# AFE.net
KiCad netlist of a schematic drawn in Altium Designer
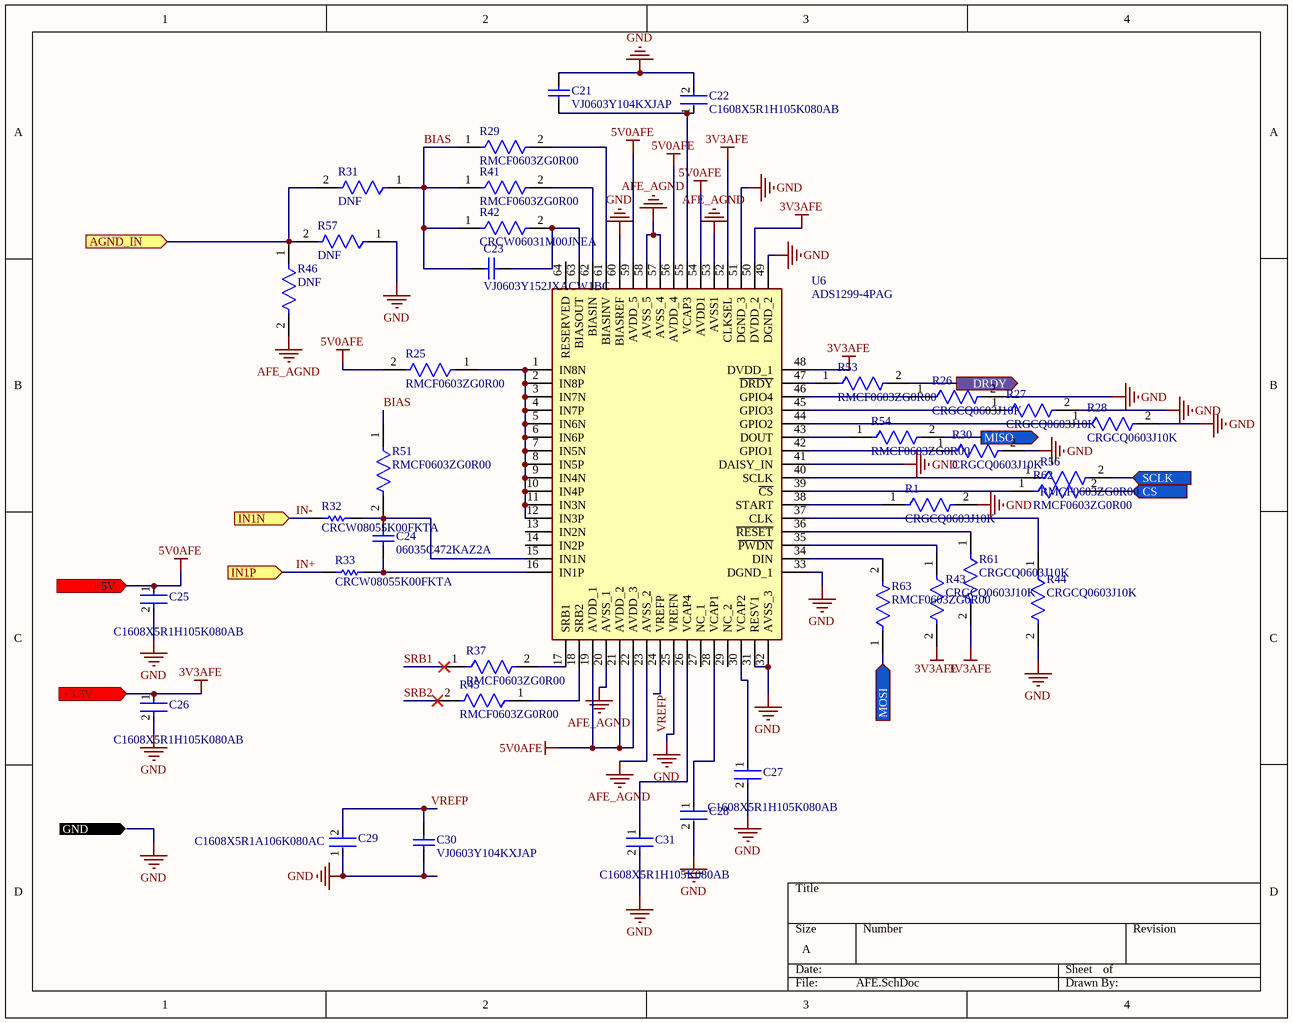
[diagram p0: AFE.SchDoc]

(export (version "E")
  (design (tool "Eeschema 10.0.6"))
  (components
    (comp (ref "C21")
      (value "VJ0603Y104KXJAP")
      (footprint "CAPC1608X92X38NL15T08")
      (fields (field (name "MANUFACTURER") "Vitramon"))
      (libsource (lib "Altium Content Vault") (part "CAP"))
    )
    (comp (ref "C22")
      (value "C1608X5R1H105K080AB")
      (footprint "FP-C1608-080-0_1-IPC_B")
      (description "Multilayer Ceramic Capacitors 1μF ±10% 50V X5R SMD 0603")
      (fields (field (name "VOLTAGE") "50V") (field (name "TOLERANCE") "10%"))
      (libsource (lib "Altium Content Vault") (part "236180d848d6139a670b325ea6854c9"))
    )
    (comp (ref "C23")
      (value "VJ0603Y152JXACW1BC")
      (footprint "CAPC1608X95X40NL15T15")
      (fields (field (name "MANUFACTURER") "Vitramon"))
      (libsource (lib "Altium Content Vault") (part "CAP"))
    )
    (comp (ref "C24")
      (value "06035C472KAZ2A")
      (footprint "CAPC1608X90X35LL15T15")
      (fields (field (name "MANUFACTURER") "AVX Interconnect / Elco"))
      (libsource (lib "Altium Content Vault") (part "CAP"))
    )
    (comp (ref "C25")
      (value "C1608X5R1H105K080AB")
      (footprint "FP-C1608-080-0_1-IPC_B")
      (description "Multilayer Ceramic Capacitors 1μF ±10% 50V X5R SMD 0603")
      (fields (field (name "VOLTAGE") "50V") (field (name "TOLERANCE") "10%"))
      (libsource (lib "Altium Content Vault") (part "236180d848d6139a670b325ea6854c9"))
    )
    (comp (ref "C26")
      (value "C1608X5R1H105K080AB")
      (footprint "FP-C1608-080-0_1-IPC_B")
      (description "Multilayer Ceramic Capacitors 1μF ±10% 50V X5R SMD 0603")
      (fields (field (name "VOLTAGE") "50V") (field (name "TOLERANCE") "10%"))
      (libsource (lib "Altium Content Vault") (part "236180d848d6139a670b325ea6854c9"))
    )
    (comp (ref "C27")
      (value "C1608X5R1H105K080AB")
      (footprint "FP-C1608-080-0_1-IPC_B")
      (description "Multilayer Ceramic Capacitors 1μF ±10% 50V X5R SMD 0603")
      (fields (field (name "VOLTAGE") "50V") (field (name "TOLERANCE") "10%"))
      (libsource (lib "Altium Content Vault") (part "236180d848d6139a670b325ea6854c9"))
    )
    (comp (ref "C28")
      (value "GRM21BR60J107ME15K")
      (footprint "FP-GRM21B-0_2-e0_2_0_7-IPC_B")
      (description "Chip Multilayer Ceramic Capacitors for General Purpose, 0805, 100uF, X5R, 15%, 20%, 6.3V")
      (fields (field (name "TOLERANCE") "20%"))
      (libsource (lib "Altium Content Vault") (part "b4654b650e69147ec39a6b967a45e02"))
    )
    (comp (ref "C29")
      (value "C1608X5R1A106K080AC")
      (footprint "FP-C1608-080-0_1-MFG")
      (description "Multilayer Ceramic Capacitors 10μF ±10% 10V X5R SMD 0603")
      (fields (field (name "VOLTAGE") "10V") (field (name "TOLERANCE") "10%"))
      (libsource (lib "Altium Content Vault") (part "236180d848d6139a670b325ea6854c9"))
    )
    (comp (ref "C30")
      (value "VJ0603Y104KXJAP")
      (footprint "CAPC1608X92X38NL15T08")
      (fields (field (name "MANUFACTURER") "Vitramon"))
      (libsource (lib "Altium Content Vault") (part "CAP"))
    )
    (comp (ref "C31")
      (value "C1608X5R1H105K080AB")
      (footprint "FP-C1608-080-0_1-IPC_B")
      (description "Multilayer Ceramic Capacitors 1μF ±10% 50V X5R SMD 0603")
      (fields (field (name "VOLTAGE") "50V") (field (name "TOLERANCE") "10%"))
      (libsource (lib "Altium Content Vault") (part "236180d848d6139a670b325ea6854c9"))
    )
    (comp (ref "R1")
      (value "CRGCQ0603J10K")
      (footprint "FP-CRGCQ0603-IPC_C")
      (description "CRGCQ 0603 10K 5%")
      (fields
        (field (name "TOLERANCE") "0.05")
        (field (name "OCTOPART") "https://octopart.com/crgcq0603j10k-te+connectivity-91018097")
      )
      (libsource (lib "Altium Content Vault") (part "1029c3af85768c4190bb7ad29bc67b5"))
    )
    (comp (ref "R25")
      (value "RMCF0603ZG0R00")
      (footprint "FP-RMCF0603-IPC_B")
      (description "0Ω ±0 0.1W 0603 Thick Film Chip Resistor AEC-Q200 compliant")
      (libsource (lib "Altium Content Vault") (part "1029c3af85768c4190bb7ad29bc67b5"))
    )
    (comp (ref "R26")
      (value "CRGCQ0603J10K")
      (footprint "FP-CRGCQ0603-IPC_C")
      (description "CRGCQ 0603 10K 5%")
      (fields
        (field (name "TOLERANCE") "0.05")
        (field (name "OCTOPART") "https://octopart.com/crgcq0603j10k-te+connectivity-91018097")
      )
      (libsource (lib "Altium Content Vault") (part "1029c3af85768c4190bb7ad29bc67b5"))
    )
    (comp (ref "R27")
      (value "CRGCQ0603J10K")
      (footprint "FP-CRGCQ0603-IPC_C")
      (description "CRGCQ 0603 10K 5%")
      (fields
        (field (name "TOLERANCE") "0.05")
        (field (name "OCTOPART") "https://octopart.com/crgcq0603j10k-te+connectivity-91018097")
      )
      (libsource (lib "Altium Content Vault") (part "1029c3af85768c4190bb7ad29bc67b5"))
    )
    (comp (ref "R28")
      (value "CRGCQ0603J10K")
      (footprint "FP-CRGCQ0603-IPC_C")
      (description "CRGCQ 0603 10K 5%")
      (fields
        (field (name "TOLERANCE") "0.05")
        (field (name "OCTOPART") "https://octopart.com/crgcq0603j10k-te+connectivity-91018097")
      )
      (libsource (lib "Altium Content Vault") (part "1029c3af85768c4190bb7ad29bc67b5"))
    )
    (comp (ref "R29")
      (value "RMCF0603ZG0R00")
      (footprint "FP-RMCF0603-IPC_B")
      (description "0Ω ±0 0.1W 0603 Thick Film Chip Resistor AEC-Q200 compliant")
      (libsource (lib "Altium Content Vault") (part "1029c3af85768c4190bb7ad29bc67b5"))
    )
    (comp (ref "R30")
      (value "CRGCQ0603J10K")
      (footprint "FP-CRGCQ0603-IPC_C")
      (description "CRGCQ 0603 10K 5%")
      (fields
        (field (name "TOLERANCE") "0.05")
        (field (name "OCTOPART") "https://octopart.com/crgcq0603j10k-te+connectivity-91018097")
      )
      (libsource (lib "Altium Content Vault") (part "1029c3af85768c4190bb7ad29bc67b5"))
    )
    (comp (ref "R31")
      (value "DNF")
      (footprint "FP-RMCF0603-IPC_B")
      (description "0Ω ±0 0.1W 0603 Thick Film Chip Resistor AEC-Q200 compliant")
      (libsource (lib "Altium Content Vault") (part "1029c3af85768c4190bb7ad29bc67b5"))
    )
    (comp (ref "R32")
      (value "CRCW08055K00FKTA")
      (footprint "RESC2013X50X30ML20T20")
      (fields (field (name "MANUFACTURER") "Vishay Dale"))
      (libsource (lib "Altium Content Vault") (part "RES"))
    )
    (comp (ref "R33")
      (value "CRCW08055K00FKTA")
      (footprint "RESC2013X50X30ML20T20")
      (fields (field (name "MANUFACTURER") "Vishay Dale"))
      (libsource (lib "Altium Content Vault") (part "RES"))
    )
    (comp (ref "R37")
      (value "RMCF0603ZG0R00")
      (footprint "FP-RMCF0603-IPC_B")
      (description "0Ω ±0 0.1W 0603 Thick Film Chip Resistor AEC-Q200 compliant")
      (libsource (lib "Altium Content Vault") (part "1029c3af85768c4190bb7ad29bc67b5"))
    )
    (comp (ref "R41")
      (value "RMCF0603ZG0R00")
      (footprint "FP-RMCF0603-IPC_B")
      (description "0Ω ±0 0.1W 0603 Thick Film Chip Resistor AEC-Q200 compliant")
      (libsource (lib "Altium Content Vault") (part "1029c3af85768c4190bb7ad29bc67b5"))
    )
    (comp (ref "R42")
      (value "CRCW06031M00JNEA")
      (footprint "FP-CRCW0603-e3-IPC_B")
      (description "RES Thick Film, 1MΩ, 5%, 0.1W, 200ppm/°C, 0603")
      (fields (field (name "TOLERANCE") "5%"))
      (libsource (lib "Altium Content Vault") (part "1029c3af85768c4190bb7ad29bc67b5"))
    )
    (comp (ref "R43")
      (value "CRGCQ0603J10K")
      (footprint "FP-CRGCQ0603-IPC_C")
      (description "CRGCQ 0603 10K 5%")
      (fields
        (field (name "TOLERANCE") "0.05")
        (field (name "OCTOPART") "https://octopart.com/crgcq0603j10k-te+connectivity-91018097")
      )
      (libsource (lib "Altium Content Vault") (part "1029c3af85768c4190bb7ad29bc67b5"))
    )
    (comp (ref "R44")
      (value "CRGCQ0603J10K")
      (footprint "FP-CRGCQ0603-IPC_C")
      (description "CRGCQ 0603 10K 5%")
      (fields
        (field (name "TOLERANCE") "0.05")
        (field (name "OCTOPART") "https://octopart.com/crgcq0603j10k-te+connectivity-91018097")
      )
      (libsource (lib "Altium Content Vault") (part "1029c3af85768c4190bb7ad29bc67b5"))
    )
    (comp (ref "R45")
      (value "RMCF0603ZG0R00")
      (footprint "FP-RMCF0603-IPC_B")
      (description "0Ω ±0 0.1W 0603 Thick Film Chip Resistor AEC-Q200 compliant")
      (libsource (lib "Altium Content Vault") (part "1029c3af85768c4190bb7ad29bc67b5"))
    )
    (comp (ref "R46")
      (value "DNF")
      (footprint "FP-RMCF0603-IPC_B")
      (description "0Ω ±0 0.1W 0603 Thick Film Chip Resistor AEC-Q200 compliant")
      (libsource (lib "Altium Content Vault") (part "1029c3af85768c4190bb7ad29bc67b5"))
    )
    (comp (ref "R51")
      (value "RMCF0603ZG0R00")
      (footprint "FP-RMCF0603-IPC_B")
      (description "0Ω ±0 0.1W 0603 Thick Film Chip Resistor AEC-Q200 compliant")
      (libsource (lib "Altium Content Vault") (part "1029c3af85768c4190bb7ad29bc67b5"))
    )
    (comp (ref "R53")
      (value "RMCF0603ZG0R00")
      (footprint "FP-RMCF0603-IPC_B")
      (description "0Ω ±0 0.1W 0603 Thick Film Chip Resistor AEC-Q200 compliant")
      (libsource (lib "Altium Content Vault") (part "1029c3af85768c4190bb7ad29bc67b5"))
    )
    (comp (ref "R54")
      (value "RMCF0603ZG0R00")
      (footprint "FP-RMCF0603-IPC_B")
      (description "0Ω ±0 0.1W 0603 Thick Film Chip Resistor AEC-Q200 compliant")
      (libsource (lib "Altium Content Vault") (part "1029c3af85768c4190bb7ad29bc67b5"))
    )
    (comp (ref "R56")
      (value "RMCF0603ZG0R00")
      (footprint "FP-RMCF0603-IPC_B")
      (description "0Ω ±0 0.1W 0603 Thick Film Chip Resistor AEC-Q200 compliant")
      (libsource (lib "Altium Content Vault") (part "1029c3af85768c4190bb7ad29bc67b5"))
    )
    (comp (ref "R57")
      (value "DNF")
      (footprint "FP-RMCF0603-IPC_B")
      (description "0Ω ±0 0.1W 0603 Thick Film Chip Resistor AEC-Q200 compliant")
      (libsource (lib "Altium Content Vault") (part "1029c3af85768c4190bb7ad29bc67b5"))
    )
    (comp (ref "R61")
      (value "CRGCQ0603J10K")
      (footprint "FP-CRGCQ0603-IPC_C")
      (description "CRGCQ 0603 10K 5%")
      (fields
        (field (name "TOLERANCE") "0.05")
        (field (name "OCTOPART") "https://octopart.com/crgcq0603j10k-te+connectivity-91018097")
      )
      (libsource (lib "Altium Content Vault") (part "1029c3af85768c4190bb7ad29bc67b5"))
    )
    (comp (ref "R62")
      (value "RMCF0603ZG0R00")
      (footprint "FP-RMCF0603-IPC_B")
      (description "0Ω ±0 0.1W 0603 Thick Film Chip Resistor AEC-Q200 compliant")
      (libsource (lib "Altium Content Vault") (part "1029c3af85768c4190bb7ad29bc67b5"))
    )
    (comp (ref "R63")
      (value "RMCF0603ZG0R00")
      (footprint "FP-RMCF0603-IPC_B")
      (description "0Ω ±0 0.1W 0603 Thick Film Chip Resistor AEC-Q200 compliant")
      (libsource (lib "Altium Content Vault") (part "1029c3af85768c4190bb7ad29bc67b5"))
    )
    (comp (ref "U6")
      (value "ADS1299-4PAG")
      (footprint "QFP50P1200X1200X120-64N")
      (description "Low-Noise, 4-Channel, 24-Bit Analog-to-Digital Converter for Biopotential Measurements")
      (fields (field (name "MOUSER PART NUMBER") "595-ADS1299-4PAG"))
      (libsource (lib "ADS1299-4PAG") (part "ADS1299-4PAG"))
    )
  )
  (nets
    (net (code "1") (name "/AGND_IN") (class "Default")
      (node (ref "R31") (pin "2") (pinfunction "2_2") (pintype "passive"))
      (node (ref "R46") (pin "1") (pinfunction "1_1") (pintype "passive"))
      (node (ref "R57") (pin "2") (pinfunction "2_2") (pintype "passive"))
    )
    (net (code "2") (name "/BIAS") (class "Default")
      (node (ref "C23") (pin "1") (pinfunction "1_1") (pintype "passive"))
      (node (ref "R29") (pin "1") (pinfunction "1_1") (pintype "passive"))
      (node (ref "R31") (pin "1") (pinfunction "1_1") (pintype "passive"))
      (node (ref "R41") (pin "1") (pinfunction "1_1") (pintype "passive"))
      (node (ref "R42") (pin "1") (pinfunction "1_1") (pintype "passive"))
      (node (ref "R51") (pin "1") (pinfunction "1_1") (pintype "passive"))
    )
    (net (code "3") (name "/CS") (class "Default")
      (node (ref "R62") (pin "2") (pinfunction "2_2") (pintype "passive"))
    )
    (net (code "4") (name "/DRDY") (class "Default")
      (node (ref "R53") (pin "2") (pinfunction "2_2") (pintype "passive"))
    )
    (net (code "5") (name "/IN+") (class "Default")
      (node (ref "R33") (pin "1") (pinfunction "1_1") (pintype "passive"))
    )
    (net (code "6") (name "/IN-") (class "Default")
      (node (ref "R32") (pin "1") (pinfunction "1_1") (pintype "passive"))
    )
    (net (code "7") (name "/MISO") (class "Default")
      (node (ref "R54") (pin "2") (pinfunction "2_2") (pintype "passive"))
    )
    (net (code "8") (name "/MOSI") (class "Default")
      (node (ref "R63") (pin "1") (pinfunction "1_1") (pintype "passive"))
    )
    (net (code "9") (name "/SCLK") (class "Default")
      (node (ref "R56") (pin "2") (pinfunction "2_2") (pintype "passive"))
    )
    (net (code "10") (name "/SRB1") (class "Default")
      (node (ref "R37") (pin "1") (pinfunction "1_1") (pintype "passive+no_connect"))
    )
    (net (code "11") (name "/SRB2") (class "Default")
      (node (ref "R45") (pin "2") (pinfunction "2_2") (pintype "passive+no_connect"))
    )
    (net (code "12") (name "/VREFP") (class "Default")
      (node (ref "C29") (pin "2") (pinfunction "2_2") (pintype "passive"))
      (node (ref "C30") (pin "2") (pinfunction "2_2") (pintype "passive"))
      (node (ref "U6") (pin "24") (pinfunction "VREFP_24") (pintype "passive"))
    )
    (net (code "13") (name "3V3AFE") (class "Default")
      (node (ref "C26") (pin "1") (pinfunction "1_1") (pintype "passive"))
      (node (ref "R43") (pin "2") (pinfunction "2_2") (pintype "passive"))
      (node (ref "R61") (pin "2") (pinfunction "2_2") (pintype "passive"))
      (node (ref "U6") (pin "48") (pinfunction "DVDD_1_48") (pintype "passive"))
      (node (ref "U6") (pin "50") (pinfunction "DVDD_2_50") (pintype "passive"))
      (node (ref "U6") (pin "52") (pinfunction "CLKSEL_52") (pintype "passive"))
    )
    (net (code "14") (name "5V0AFE") (class "Default")
      (node (ref "C25") (pin "1") (pinfunction "1_1") (pintype "passive"))
      (node (ref "R25") (pin "2") (pinfunction "2_2") (pintype "passive"))
      (node (ref "U6") (pin "19") (pinfunction "AVDD_1_19") (pintype "passive"))
      (node (ref "U6") (pin "21") (pinfunction "AVDD_2_21") (pintype "passive"))
      (node (ref "U6") (pin "22") (pinfunction "AVDD_3_22") (pintype "passive"))
      (node (ref "U6") (pin "54") (pinfunction "AVDD1_54") (pintype "passive"))
      (node (ref "U6") (pin "56") (pinfunction "AVDD_4_56") (pintype "passive"))
      (node (ref "U6") (pin "59") (pinfunction "AVDD_5_59") (pintype "passive"))
    )
    (net (code "15") (name "AFE_AGND") (class "Default")
      (node (ref "R46") (pin "2") (pinfunction "2_2") (pintype "passive"))
      (node (ref "U6") (pin "20") (pinfunction "AVSS_1_20") (pintype "passive"))
      (node (ref "U6") (pin "23") (pinfunction "AVSS_2_23") (pintype "passive"))
      (node (ref "U6") (pin "53") (pinfunction "AVSS1_53") (pintype "passive"))
      (node (ref "U6") (pin "57") (pinfunction "AVSS_4_57") (pintype "passive"))
      (node (ref "U6") (pin "58") (pinfunction "AVSS_5_58") (pintype "passive"))
    )
    (net (code "16") (name "GND") (class "Default")
      (node (ref "C21") (pin "2") (pinfunction "2_2") (pintype "passive"))
      (node (ref "C22") (pin "2") (pinfunction "2_2") (pintype "passive"))
      (node (ref "C25") (pin "2") (pinfunction "2_2") (pintype "passive"))
      (node (ref "C26") (pin "2") (pinfunction "2_2") (pintype "passive"))
      (node (ref "C27") (pin "2") (pinfunction "2_2") (pintype "passive"))
      (node (ref "C28") (pin "2") (pinfunction "2_2") (pintype "passive"))
      (node (ref "C29") (pin "1") (pinfunction "1_1") (pintype "passive"))
      (node (ref "C30") (pin "1") (pinfunction "1_1") (pintype "passive"))
      (node (ref "C31") (pin "2") (pinfunction "2_2") (pintype "passive"))
      (node (ref "R1") (pin "2") (pinfunction "2_2") (pintype "passive"))
      (node (ref "R26") (pin "2") (pinfunction "2_2") (pintype "passive"))
      (node (ref "R27") (pin "2") (pinfunction "2_2") (pintype "passive"))
      (node (ref "R28") (pin "2") (pinfunction "2_2") (pintype "passive"))
      (node (ref "R30") (pin "2") (pinfunction "2_2") (pintype "passive"))
      (node (ref "R44") (pin "2") (pinfunction "2_2") (pintype "passive"))
      (node (ref "R57") (pin "1") (pinfunction "1_1") (pintype "passive"))
      (node (ref "U6") (pin "25") (pinfunction "VREFN_25") (pintype "passive"))
      (node (ref "U6") (pin "31") (pinfunction "RESV1_31") (pintype "passive"))
      (node (ref "U6") (pin "32") (pinfunction "AVSS_3_32") (pintype "passive"))
      (node (ref "U6") (pin "33") (pinfunction "DGND_1_33") (pintype "passive"))
      (node (ref "U6") (pin "41") (pinfunction "DAISY_IN_41") (pintype "passive"))
      (node (ref "U6") (pin "49") (pinfunction "DGND_2_49") (pintype "passive"))
      (node (ref "U6") (pin "51") (pinfunction "DGND_3_51") (pintype "passive"))
      (node (ref "U6") (pin "60") (pinfunction "BIASREF_60") (pintype "passive"))
    )
    (net (code "17") (name "Net-(U6-BIASIN)") (class "Default")
      (node (ref "R41") (pin "2") (pinfunction "2_2") (pintype "passive"))
      (node (ref "U6") (pin "62") (pinfunction "BIASIN_62") (pintype "passive"))
    )
    (net (code "18") (name "Net-(U6-BIASINV)") (class "Default")
      (node (ref "R29") (pin "2") (pinfunction "2_2") (pintype "passive"))
      (node (ref "U6") (pin "61") (pinfunction "BIASINV_61") (pintype "passive"))
    )
    (net (code "19") (name "Net-(U6-BIASOUT)") (class "Default")
      (node (ref "C23") (pin "2") (pinfunction "2_2") (pintype "passive"))
      (node (ref "R42") (pin "2") (pinfunction "2_2") (pintype "passive"))
      (node (ref "U6") (pin "63") (pinfunction "BIASOUT_63") (pintype "passive"))
    )
    (net (code "20") (name "Net-(U6-CLK)") (class "Default")
      (node (ref "R44") (pin "1") (pinfunction "1_1") (pintype "passive"))
      (node (ref "U6") (pin "37") (pinfunction "CLK_37") (pintype "passive"))
    )
    (net (code "21") (name "Net-(U6-DIN)") (class "Default")
      (node (ref "R63") (pin "2") (pinfunction "2_2") (pintype "passive"))
      (node (ref "U6") (pin "34") (pinfunction "DIN_34") (pintype "passive"))
    )
    (net (code "22") (name "Net-(U6-DOUT)") (class "Default")
      (node (ref "R54") (pin "1") (pinfunction "1_1") (pintype "passive"))
      (node (ref "U6") (pin "43") (pinfunction "DOUT_43") (pintype "passive"))
    )
    (net (code "23") (name "Net-(U6-GPIO1)") (class "Default")
      (node (ref "R30") (pin "1") (pinfunction "1_1") (pintype "passive"))
      (node (ref "U6") (pin "42") (pinfunction "GPIO1_42") (pintype "passive"))
    )
    (net (code "24") (name "Net-(U6-GPIO2)") (class "Default")
      (node (ref "R28") (pin "1") (pinfunction "1_1") (pintype "passive"))
      (node (ref "U6") (pin "44") (pinfunction "GPIO2_44") (pintype "passive"))
    )
    (net (code "25") (name "Net-(U6-GPIO3)") (class "Default")
      (node (ref "R27") (pin "1") (pinfunction "1_1") (pintype "passive"))
      (node (ref "U6") (pin "45") (pinfunction "GPIO3_45") (pintype "passive"))
    )
    (net (code "26") (name "Net-(U6-GPIO4)") (class "Default")
      (node (ref "R26") (pin "1") (pinfunction "1_1") (pintype "passive"))
      (node (ref "U6") (pin "46") (pinfunction "GPIO4_46") (pintype "passive"))
    )
    (net (code "27") (name "Net-(U6-IN1N)") (class "Default")
      (node (ref "C24") (pin "1") (pinfunction "1_1") (pintype "passive"))
      (node (ref "R32") (pin "2") (pinfunction "2_2") (pintype "passive"))
      (node (ref "R51") (pin "2") (pinfunction "2_2") (pintype "passive"))
      (node (ref "U6") (pin "15") (pinfunction "IN1N_15") (pintype "passive"))
    )
    (net (code "28") (name "Net-(U6-IN1P)") (class "Default")
      (node (ref "C24") (pin "2") (pinfunction "2_2") (pintype "passive"))
      (node (ref "R33") (pin "2") (pinfunction "2_2") (pintype "passive"))
      (node (ref "U6") (pin "16") (pinfunction "IN1P_16") (pintype "passive"))
    )
    (net (code "29") (name "Net-(U6-IN3N)") (class "Default")
      (node (ref "R25") (pin "1") (pinfunction "1_1") (pintype "passive"))
      (node (ref "U6") (pin "1") (pinfunction "IN8N_1") (pintype "passive"))
      (node (ref "U6") (pin "10") (pinfunction "IN4P_10") (pintype "passive"))
      (node (ref "U6") (pin "11") (pinfunction "IN3N_11") (pintype "passive"))
      (node (ref "U6") (pin "12") (pinfunction "IN3P_12") (pintype "passive"))
      (node (ref "U6") (pin "2") (pinfunction "IN8P_2") (pintype "passive"))
      (node (ref "U6") (pin "3") (pinfunction "IN7N_3") (pintype "passive"))
      (node (ref "U6") (pin "4") (pinfunction "IN7P_4") (pintype "passive"))
      (node (ref "U6") (pin "5") (pinfunction "IN6N_5") (pintype "passive"))
      (node (ref "U6") (pin "6") (pinfunction "IN6P_6") (pintype "passive"))
      (node (ref "U6") (pin "7") (pinfunction "IN5N_7") (pintype "passive"))
      (node (ref "U6") (pin "8") (pinfunction "IN5P_8") (pintype "passive"))
      (node (ref "U6") (pin "9") (pinfunction "IN4N_9") (pintype "passive"))
    )
    (net (code "30") (name "Net-(U6-SCLK)") (class "Default")
      (node (ref "R56") (pin "1") (pinfunction "1_1") (pintype "passive"))
      (node (ref "U6") (pin "40") (pinfunction "SCLK_40") (pintype "passive"))
    )
    (net (code "31") (name "Net-(U6-SRB1)") (class "Default")
      (node (ref "R37") (pin "2") (pinfunction "2_2") (pintype "passive"))
      (node (ref "U6") (pin "17") (pinfunction "SRB1_17") (pintype "passive"))
    )
    (net (code "32") (name "Net-(U6-SRB2)") (class "Default")
      (node (ref "R45") (pin "1") (pinfunction "1_1") (pintype "passive"))
      (node (ref "U6") (pin "18") (pinfunction "SRB2_18") (pintype "passive"))
    )
    (net (code "33") (name "Net-(U6-START)") (class "Default")
      (node (ref "R1") (pin "1") (pinfunction "1_1") (pintype "passive"))
      (node (ref "U6") (pin "38") (pinfunction "START_38") (pintype "passive"))
    )
    (net (code "34") (name "Net-(U6-VCAP1)") (class "Default")
      (node (ref "C28") (pin "1") (pinfunction "1_1") (pintype "passive"))
      (node (ref "U6") (pin "28") (pinfunction "VCAP1_28") (pintype "passive"))
    )
    (net (code "35") (name "Net-(U6-VCAP2)") (class "Default")
      (node (ref "C27") (pin "1") (pinfunction "1_1") (pintype "passive"))
      (node (ref "U6") (pin "30") (pinfunction "VCAP2_30") (pintype "passive"))
    )
    (net (code "36") (name "Net-(U6-VCAP3)") (class "Default")
      (node (ref "C21") (pin "1") (pinfunction "1_1") (pintype "passive"))
      (node (ref "C22") (pin "1") (pinfunction "1_1") (pintype "passive"))
      (node (ref "U6") (pin "55") (pinfunction "VCAP3_55") (pintype "passive"))
    )
    (net (code "37") (name "Net-(U6-VCAP4)") (class "Default")
      (node (ref "C31") (pin "1") (pinfunction "1_1") (pintype "passive"))
      (node (ref "U6") (pin "26") (pinfunction "VCAP4_26") (pintype "passive"))
    )
    (net (code "38") (name "Net-(U6-~{CS})") (class "Default")
      (node (ref "R62") (pin "1") (pinfunction "1_1") (pintype "passive"))
      (node (ref "U6") (pin "39") (pinfunction "~{CS}_39") (pintype "passive"))
    )
    (net (code "39") (name "Net-(U6-~{DRDY})") (class "Default")
      (node (ref "R53") (pin "1") (pinfunction "1_1") (pintype "passive"))
      (node (ref "U6") (pin "47") (pinfunction "~{DRDY}_47") (pintype "passive"))
    )
    (net (code "40") (name "Net-(U6-~{PWDN})") (class "Default")
      (node (ref "R43") (pin "1") (pinfunction "1_1") (pintype "passive"))
      (node (ref "U6") (pin "35") (pinfunction "~{PWDN}_35") (pintype "passive"))
    )
    (net (code "41") (name "Net-(U6-~{RESET})") (class "Default")
      (node (ref "R61") (pin "1") (pinfunction "1_1") (pintype "passive"))
      (node (ref "U6") (pin "36") (pinfunction "~{RESET}_36") (pintype "passive"))
    )
    (net (code "42") (name "unconnected-(U6-IN2N-Pad13)") (class "Default")
      (node (ref "U6") (pin "13") (pinfunction "IN2N_13") (pintype "passive"))
    )
    (net (code "43") (name "unconnected-(U6-IN2P-Pad14)") (class "Default")
      (node (ref "U6") (pin "14") (pinfunction "IN2P_14") (pintype "passive"))
    )
    (net (code "44") (name "unconnected-(U6-NC_1-Pad27)") (class "Default")
      (node (ref "U6") (pin "27") (pinfunction "NC_1_27") (pintype "passive"))
    )
    (net (code "45") (name "unconnected-(U6-NC_2-Pad29)") (class "Default")
      (node (ref "U6") (pin "29") (pinfunction "NC_2_29") (pintype "passive"))
    )
    (net (code "46") (name "unconnected-(U6-RESERVED-Pad64)") (class "Default")
      (node (ref "U6") (pin "64") (pinfunction "RESERVED_64") (pintype "passive"))
    )
  )
)
